# EAT0003.net
KiCad netlist of a schematic drawn in EAGLE
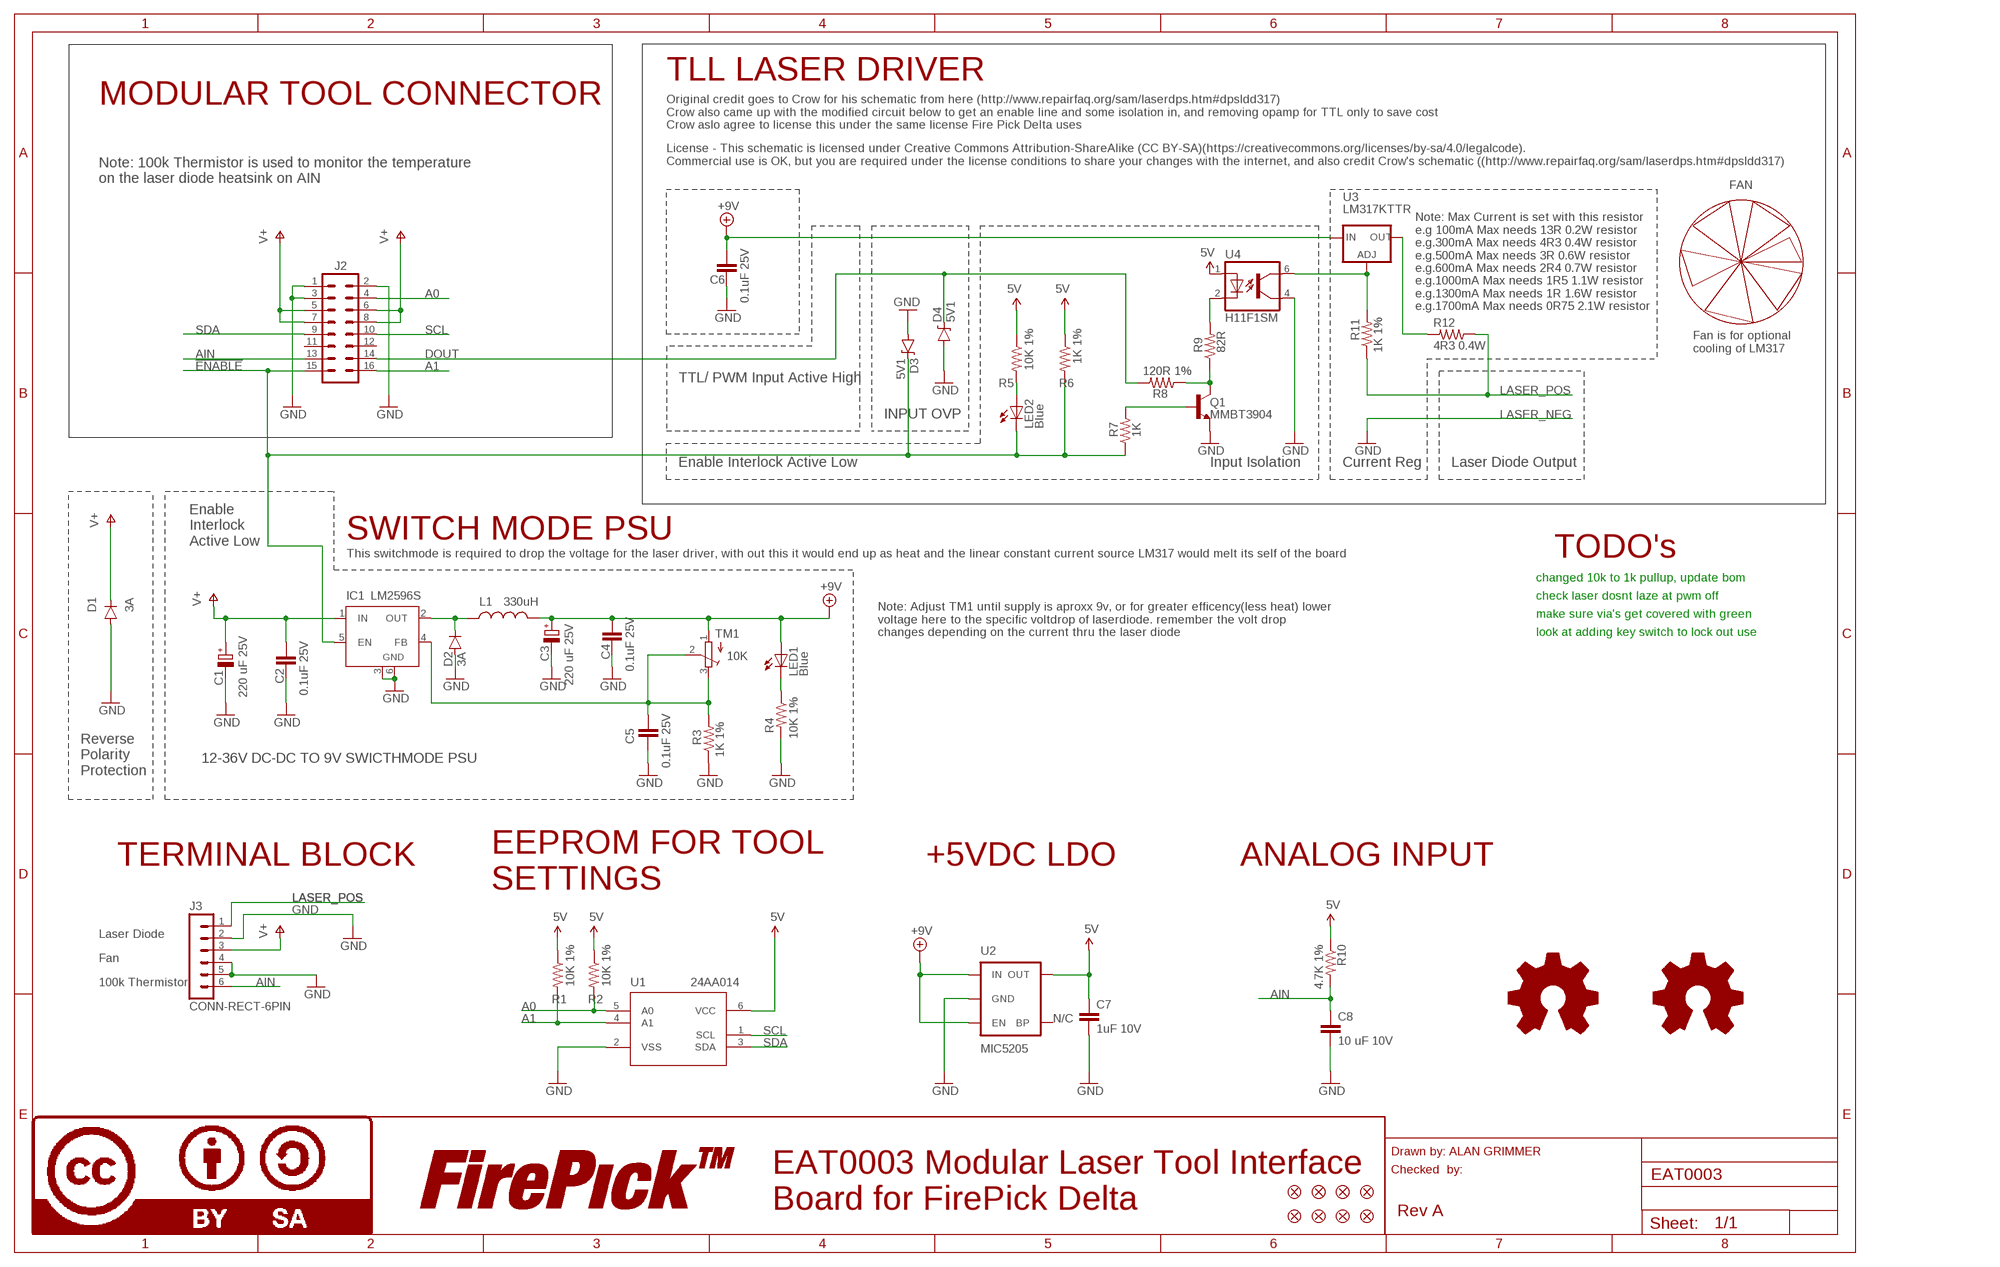
[diagram p0: schematic, sheet 1]

(export (version "E")
  (design (tool "Eeschema 10.0.6"))
  (components
    (comp (ref "C1")
      (value "220 uF 25V")
      (footprint "eagle-import:UD-8X10_NICHICON")
      (libsource (lib "eagle-import") (part "CPOL-EUUD-8X10"))
    )
    (comp (ref "C2")
      (value "0.1uF 25V")
      (footprint "eagle-import:0603-CAP")
      (libsource (lib "eagle-import") (part "CAP0603-CAP"))
    )
    (comp (ref "C3")
      (value "220 uF 25V")
      (footprint "eagle-import:UD-8X10_NICHICON")
      (libsource (lib "eagle-import") (part "CPOL-EUUD-8X10"))
    )
    (comp (ref "C4")
      (value "0.1uF 25V")
      (footprint "eagle-import:0603-CAP")
      (libsource (lib "eagle-import") (part "CAP0603-CAP"))
    )
    (comp (ref "C5")
      (value "0.1uF 25V")
      (footprint "eagle-import:0603-CAP")
      (libsource (lib "eagle-import") (part "CAP0603-CAP"))
    )
    (comp (ref "C6")
      (value "0.1uF 25V")
      (footprint "eagle-import:0603-CAP")
      (libsource (lib "eagle-import") (part "CAP0603-CAP"))
    )
    (comp (ref "C7")
      (value "1uF 10V")
      (footprint "eagle-import:0603-CAP")
      (libsource (lib "eagle-import") (part "CAP0603-CAP"))
    )
    (comp (ref "C8")
      (value "10 uF 10V")
      (footprint "eagle-import:0805")
      (libsource (lib "eagle-import") (part "CAP0805"))
    )
    (comp (ref "D1")
      (value "3A")
      (footprint "eagle-import:SMA-DIODE")
      (libsource (lib "eagle-import") (part "DIODESMA"))
    )
    (comp (ref "D2")
      (value "3A")
      (footprint "eagle-import:SMA-DIODE")
      (libsource (lib "eagle-import") (part "DIODESMA"))
    )
    (comp (ref "D3")
      (value "5V1")
      (footprint "eagle-import:SOD-323")
      (libsource (lib "eagle-import") (part "DIODE-ZENER5.6V"))
    )
    (comp (ref "D4")
      (value "5V1")
      (footprint "eagle-import:SOD-323")
      (libsource (lib "eagle-import") (part "DIODE-ZENER5.6V"))
    )
    (comp (ref "FAN1")
      (value "FAN_30MM")
      (footprint "eagle-import:FAN_30MM_X_30MM")
      (libsource (lib "eagle-import") (part "FAN_30MM"))
    )
    (comp (ref "FID1")
      (value "FIDUCIAL1X2")
      (footprint "eagle-import:FIDUCIAL-1X2")
      (libsource (lib "eagle-import") (part "FIDUCIAL1X2"))
    )
    (comp (ref "FID2")
      (value "FIDUCIAL1X2")
      (footprint "eagle-import:FIDUCIAL-1X2")
      (libsource (lib "eagle-import") (part "FIDUCIAL1X2"))
    )
    (comp (ref "FID3")
      (value "FIDUCIAL1X2")
      (footprint "eagle-import:FIDUCIAL-1X2")
      (libsource (lib "eagle-import") (part "FIDUCIAL1X2"))
    )
    (comp (ref "FID4")
      (value "FIDUCIAL1X2")
      (footprint "eagle-import:FIDUCIAL-1X2")
      (libsource (lib "eagle-import") (part "FIDUCIAL1X2"))
    )
    (comp (ref "FID5")
      (value "FIDUCIAL1X2")
      (footprint "eagle-import:FIDUCIAL-1X2")
      (libsource (lib "eagle-import") (part "FIDUCIAL1X2"))
    )
    (comp (ref "FID6")
      (value "FIDUCIAL1X2")
      (footprint "eagle-import:FIDUCIAL-1X2")
      (libsource (lib "eagle-import") (part "FIDUCIAL1X2"))
    )
    (comp (ref "FID7")
      (value "FIDUCIAL1X2")
      (footprint "eagle-import:FIDUCIAL-1X2")
      (libsource (lib "eagle-import") (part "FIDUCIAL1X2"))
    )
    (comp (ref "FID8")
      (value "FIDUCIAL1X2")
      (footprint "eagle-import:FIDUCIAL-1X2")
      (libsource (lib "eagle-import") (part "FIDUCIAL1X2"))
    )
    (comp (ref "IC1")
      (value "LM2596S")
      (footprint "eagle-import:TO263-5")
      (libsource (lib "eagle-import") (part "LM2596S"))
    )
    (comp (ref "J2")
      (value "CONN-RECT-16PIN-2ROWSIDE")
      (footprint "eagle-import:CONN-RECT-2.54MM-16PIN-2ROW-SIDE")
      (libsource (lib "eagle-import") (part "CONN-RECT-16PIN-2ROWSIDE"))
    )
    (comp (ref "J3")
      (value "CONN-RECT-6PIN")
      (footprint "eagle-import:CONN-OSTTE_6PIN")
      (libsource (lib "eagle-import") (part "CONN-RECT-6PIN"))
    )
    (comp (ref "L1")
      (value "330uH")
      (footprint "eagle-import:CDRH125")
      (libsource (lib "eagle-import") (part "INDUCTORPWR"))
    )
    (comp (ref "LED1")
      (value "Blue")
      (footprint "eagle-import:CHIPLED_0603")
      (libsource (lib "eagle-import") (part "LEDCHIPLED_0603"))
    )
    (comp (ref "LED2")
      (value "Blue")
      (footprint "eagle-import:CHIPLED_0603")
      (libsource (lib "eagle-import") (part "LEDCHIPLED_0603"))
    )
    (comp (ref "LOGO1")
      (value "LOGO-CC-BY-SASMALL")
      (footprint "eagle-import:LOGO-CC-BY-SA-SMALL")
      (libsource (lib "eagle-import") (part "LOGO-CC-BY-SASMALL"))
    )
    (comp (ref "LOGO2")
      (value "LOGO-FIREPICKSMALL")
      (footprint "eagle-import:LOGO-FIREPICK-SMALL")
      (libsource (lib "eagle-import") (part "LOGO-FIREPICKSMALL"))
    )
    (comp (ref "LOGO3")
      (value "LOGO-OSHWSMALL")
      (footprint "eagle-import:LOGO-OSHW-SMALL")
      (libsource (lib "eagle-import") (part "LOGO-OSHWSMALL"))
    )
    (comp (ref "LOGO4")
      (value "LOGO-OSHWSMALL")
      (footprint "eagle-import:LOGO-OSHW-SMALL")
      (libsource (lib "eagle-import") (part "LOGO-OSHWSMALL"))
    )
    (comp (ref "LOGO5")
      (value "LOGO-CC-BY-SASMALL")
      (footprint "eagle-import:LOGO-CC-BY-SA-SMALL")
      (libsource (lib "eagle-import") (part "LOGO-CC-BY-SASMALL"))
    )
    (comp (ref "LOGO6")
      (value "LOGO-FIREPICKSMALL")
      (footprint "eagle-import:LOGO-FIREPICK-SMALL")
      (libsource (lib "eagle-import") (part "LOGO-FIREPICKSMALL"))
    )
    (comp (ref "Q1")
      (value "MMBT3904")
      (footprint "eagle-import:SOT23-3")
      (libsource (lib "eagle-import") (part "TRANSISTOR_NPNMMBT2222A"))
    )
    (comp (ref "R1")
      (value "10K 1%")
      (footprint "eagle-import:0603-RES")
      (libsource (lib "eagle-import") (part "RESISTOR0603-RES"))
    )
    (comp (ref "R2")
      (value "10K 1%")
      (footprint "eagle-import:0603-RES")
      (libsource (lib "eagle-import") (part "RESISTOR0603-RES"))
    )
    (comp (ref "R3")
      (value "1K 1%")
      (footprint "eagle-import:0603-RES")
      (libsource (lib "eagle-import") (part "RESISTOR0603-RES"))
    )
    (comp (ref "R4")
      (value "10K 1%")
      (footprint "eagle-import:0603-RES")
      (libsource (lib "eagle-import") (part "RESISTOR0603-RES"))
    )
    (comp (ref "R5")
      (value "10K 1%")
      (footprint "eagle-import:0603-RES")
      (libsource (lib "eagle-import") (part "RESISTOR0603-RES"))
    )
    (comp (ref "R6")
      (value "1K 1%")
      (footprint "eagle-import:0603-RES")
      (libsource (lib "eagle-import") (part "RESISTOR0603-RES"))
    )
    (comp (ref "R7")
      (value "1K")
      (footprint "eagle-import:0603-RES")
      (libsource (lib "eagle-import") (part "RESISTOR0603-RES"))
    )
    (comp (ref "R8")
      (value "120R 1%")
      (footprint "eagle-import:0603-RES")
      (libsource (lib "eagle-import") (part "RESISTOR0603-RES"))
    )
    (comp (ref "R9")
      (value "82R")
      (footprint "eagle-import:0603-RES")
      (libsource (lib "eagle-import") (part "RESISTOR0603-RES"))
    )
    (comp (ref "R10")
      (value "4.7K 1%")
      (footprint "eagle-import:0603-RES")
      (libsource (lib "eagle-import") (part "RESISTOR0603-RES"))
    )
    (comp (ref "R11")
      (value "1K 1%")
      (footprint "eagle-import:0603-RES")
      (libsource (lib "eagle-import") (part "RESISTOR0603-RES"))
    )
    (comp (ref "R12")
      (value "4R3 0.4W")
      (footprint "eagle-import:R2512")
      (libsource (lib "eagle-import") (part "RESISTOR2512"))
    )
    (comp (ref "TM1")
      (value "10K")
      (footprint "eagle-import:TC33X")
      (libsource (lib "eagle-import") (part "TRIMPOTTC33X"))
    )
    (comp (ref "U1")
      (value "24AA014")
      (footprint "eagle-import:SOT23-6")
      (libsource (lib "eagle-import") (part "IC-24AA014"))
    )
    (comp (ref "U2")
      (value "MIC5205")
      (footprint "eagle-import:SOT23-5")
      (libsource (lib "eagle-import") (part "MIC52055V"))
    )
    (comp (ref "U3")
      (value "LM317KTTR")
      (footprint "eagle-import:D2PAK-3")
      (libsource (lib "eagle-import") (part "V_REG_317"))
    )
    (comp (ref "U4")
      (value "H11F1SM")
      (footprint "eagle-import:DIL6-SMD")
      (libsource (lib "eagle-import") (part "H11F1DIL6SMD"))
    )
  )
  (nets
    (net (code "1") (name "+9V") (class "Default")
      (node (ref "C3") (pin "+") (pinfunction "+_+") (pintype "passive"))
      (node (ref "C4") (pin "1") (pinfunction "1_1") (pintype "passive"))
      (node (ref "C6") (pin "1") (pinfunction "1_1") (pintype "passive"))
      (node (ref "L1") (pin "2") (pinfunction "2_2") (pintype "passive"))
      (node (ref "LED1") (pin "A") (pinfunction "A_A") (pintype "passive"))
      (node (ref "TM1") (pin "1") (pinfunction "A_1") (pintype "passive"))
      (node (ref "U2") (pin "1") (pinfunction "IN_1") (pintype "input"))
      (node (ref "U2") (pin "3") (pinfunction "EN_3") (pintype "input"))
      (node (ref "U3") (pin "3") (pinfunction "IN_3") (pintype "input"))
    )
    (net (code "2") (name "/A0") (class "Default")
      (node (ref "J2") (pin "4") (pinfunction "4_4") (pintype "passive"))
      (node (ref "R2") (pin "2") (pinfunction "2_2") (pintype "passive"))
      (node (ref "U1") (pin "5") (pinfunction "A0_5") (pintype "bidirectional"))
    )
    (net (code "3") (name "/A1") (class "Default")
      (node (ref "J2") (pin "16") (pinfunction "16_16") (pintype "passive"))
      (node (ref "R1") (pin "2") (pinfunction "2_2") (pintype "passive"))
      (node (ref "U1") (pin "4") (pinfunction "A1_4") (pintype "bidirectional"))
    )
    (net (code "4") (name "/AIN") (class "Default")
      (node (ref "C8") (pin "1") (pinfunction "1_1") (pintype "passive"))
      (node (ref "J2") (pin "13") (pinfunction "13_13") (pintype "passive"))
      (node (ref "J3") (pin "6") (pinfunction "6_6") (pintype "passive"))
      (node (ref "R10") (pin "2") (pinfunction "2_2") (pintype "passive"))
    )
    (net (code "5") (name "/DOUT") (class "Default")
      (node (ref "D4") (pin "C") (pinfunction "C_C") (pintype "passive"))
      (node (ref "J2") (pin "14") (pinfunction "14_14") (pintype "passive"))
      (node (ref "R8") (pin "2") (pinfunction "2_2") (pintype "passive"))
    )
    (net (code "6") (name "/LASER_POS") (class "Default")
      (node (ref "J3") (pin "1") (pinfunction "1_1") (pintype "passive"))
      (node (ref "R11") (pin "1") (pinfunction "1_1") (pintype "passive"))
      (node (ref "R12") (pin "1") (pinfunction "1_1") (pintype "passive"))
    )
    (net (code "7") (name "/SCL") (class "Default")
      (node (ref "J2") (pin "10") (pinfunction "10_10") (pintype "passive"))
      (node (ref "U1") (pin "1") (pinfunction "SCL_1") (pintype "bidirectional"))
    )
    (net (code "8") (name "/SDA") (class "Default")
      (node (ref "J2") (pin "9") (pinfunction "9_9") (pintype "passive"))
      (node (ref "U1") (pin "3") (pinfunction "SDA_3") (pintype "bidirectional"))
    )
    (net (code "9") (name "/~{ENABLE}") (class "Default")
      (node (ref "D3") (pin "C") (pinfunction "C_C") (pintype "passive"))
      (node (ref "IC1") (pin "5") (pinfunction "EN_5") (pintype "input"))
      (node (ref "J2") (pin "15") (pinfunction "15_15") (pintype "passive"))
      (node (ref "LED2") (pin "C") (pinfunction "C_C") (pintype "passive"))
      (node (ref "R6") (pin "2") (pinfunction "2_2") (pintype "passive"))
      (node (ref "R7") (pin "1") (pinfunction "1_1") (pintype "passive"))
    )
    (net (code "10") (name "5V") (class "Default")
      (node (ref "C7") (pin "1") (pinfunction "1_1") (pintype "passive"))
      (node (ref "R1") (pin "1") (pinfunction "1_1") (pintype "passive"))
      (node (ref "R10") (pin "1") (pinfunction "1_1") (pintype "passive"))
      (node (ref "R2") (pin "1") (pinfunction "1_1") (pintype "passive"))
      (node (ref "R5") (pin "1") (pinfunction "1_1") (pintype "passive"))
      (node (ref "R6") (pin "1") (pinfunction "1_1") (pintype "passive"))
      (node (ref "U1") (pin "6") (pinfunction "VCC_6") (pintype "bidirectional"))
      (node (ref "U2") (pin "5") (pinfunction "OUT_5") (pintype "passive"))
      (node (ref "U4") (pin "1") (pinfunction "A_1") (pintype "passive"))
    )
    (net (code "11") (name "GND") (class "Default")
      (node (ref "C1") (pin "-") (pinfunction "-_-") (pintype "passive"))
      (node (ref "C2") (pin "2") (pinfunction "2_2") (pintype "passive"))
      (node (ref "C3") (pin "-") (pinfunction "-_-") (pintype "passive"))
      (node (ref "C4") (pin "2") (pinfunction "2_2") (pintype "passive"))
      (node (ref "C5") (pin "2") (pinfunction "2_2") (pintype "passive"))
      (node (ref "C6") (pin "2") (pinfunction "2_2") (pintype "passive"))
      (node (ref "C7") (pin "2") (pinfunction "2_2") (pintype "passive"))
      (node (ref "C8") (pin "2") (pinfunction "2_2") (pintype "passive"))
      (node (ref "D1") (pin "A") (pinfunction "A_A") (pintype "passive"))
      (node (ref "D2") (pin "A") (pinfunction "A_A") (pintype "passive"))
      (node (ref "D3") (pin "A") (pinfunction "A_A") (pintype "passive"))
      (node (ref "D4") (pin "A") (pinfunction "A_A") (pintype "passive"))
      (node (ref "IC1") (pin "3") (pinfunction "GND_3") (pintype "power_in"))
      (node (ref "IC1") (pin "6") (pinfunction "GND_6") (pintype "power_in"))
      (node (ref "J2") (pin "1") (pinfunction "1_1") (pintype "passive"))
      (node (ref "J2") (pin "2") (pinfunction "2_2") (pintype "passive"))
      (node (ref "J2") (pin "3") (pinfunction "3_3") (pintype "passive"))
      (node (ref "J3") (pin "2") (pinfunction "2_2") (pintype "passive"))
      (node (ref "J3") (pin "4") (pinfunction "4_4") (pintype "passive"))
      (node (ref "J3") (pin "5") (pinfunction "5_5") (pintype "passive"))
      (node (ref "Q1") (pin "2") (pinfunction "E_2") (pintype "passive"))
      (node (ref "R3") (pin "1") (pinfunction "1_1") (pintype "passive"))
      (node (ref "R4") (pin "2") (pinfunction "2_2") (pintype "passive"))
      (node (ref "U1") (pin "2") (pinfunction "VSS_2") (pintype "bidirectional"))
      (node (ref "U2") (pin "2") (pinfunction "GND_2") (pintype "input"))
      (node (ref "U4") (pin "4") (pinfunction "EMIT_4") (pintype "passive"))
    )
    (net (code "12") (name "Net-(IC1-FB)") (class "Default")
      (node (ref "C5") (pin "1") (pinfunction "1_1") (pintype "passive"))
      (node (ref "IC1") (pin "4") (pinfunction "FB_4") (pintype "input"))
      (node (ref "R3") (pin "2") (pinfunction "2_2") (pintype "passive"))
      (node (ref "TM1") (pin "2") (pinfunction "S_2") (pintype "passive"))
      (node (ref "TM1") (pin "3") (pinfunction "E_3") (pintype "passive"))
    )
    (net (code "13") (name "Net-(IC1-OUT)") (class "Default")
      (node (ref "D2") (pin "C") (pinfunction "C_C") (pintype "passive"))
      (node (ref "IC1") (pin "2") (pinfunction "OUT_2") (pintype "output"))
      (node (ref "L1") (pin "1") (pinfunction "1_1") (pintype "passive"))
    )
    (net (code "14") (name "Net-(LED1-PadC)") (class "Default")
      (node (ref "LED1") (pin "C") (pinfunction "C_C") (pintype "passive"))
      (node (ref "R4") (pin "1") (pinfunction "1_1") (pintype "passive"))
    )
    (net (code "15") (name "Net-(LED2-PadA)") (class "Default")
      (node (ref "LED2") (pin "A") (pinfunction "A_A") (pintype "passive"))
      (node (ref "R5") (pin "2") (pinfunction "2_2") (pintype "passive"))
    )
    (net (code "16") (name "Net-(Q1-B)") (class "Default")
      (node (ref "Q1") (pin "1") (pinfunction "B_1") (pintype "passive"))
      (node (ref "R7") (pin "2") (pinfunction "2_2") (pintype "passive"))
    )
    (net (code "17") (name "Net-(Q1-C)") (class "Default")
      (node (ref "Q1") (pin "3") (pinfunction "C_3") (pintype "passive"))
      (node (ref "R8") (pin "1") (pinfunction "1_1") (pintype "passive"))
      (node (ref "R9") (pin "1") (pinfunction "1_1") (pintype "passive"))
    )
    (net (code "18") (name "Net-(R12-Pad2)") (class "Default")
      (node (ref "R12") (pin "2") (pinfunction "2_2") (pintype "passive"))
      (node (ref "U3") (pin "2") (pinfunction "OUT_2") (pintype "output"))
      (node (ref "U3") (pin "PAD") (pinfunction "OUT_PAD") (pintype "output"))
    )
    (net (code "19") (name "Net-(U3-ADJ)") (class "Default")
      (node (ref "R11") (pin "2") (pinfunction "2_2") (pintype "passive"))
      (node (ref "U3") (pin "1") (pinfunction "ADJ_1") (pintype "input"))
      (node (ref "U4") (pin "6") (pinfunction "COL_6") (pintype "passive"))
    )
    (net (code "20") (name "Net-(U4-C)") (class "Default")
      (node (ref "R9") (pin "2") (pinfunction "2_2") (pintype "passive"))
      (node (ref "U4") (pin "2") (pinfunction "C_2") (pintype "passive"))
    )
    (net (code "21") (name "V+") (class "Default")
      (node (ref "C1") (pin "+") (pinfunction "+_+") (pintype "passive"))
      (node (ref "C2") (pin "1") (pinfunction "1_1") (pintype "passive"))
      (node (ref "D1") (pin "C") (pinfunction "C_C") (pintype "passive"))
      (node (ref "IC1") (pin "1") (pinfunction "IN_1") (pintype "input"))
      (node (ref "J2") (pin "5") (pinfunction "5_5") (pintype "passive"))
      (node (ref "J2") (pin "6") (pinfunction "6_6") (pintype "passive"))
      (node (ref "J2") (pin "7") (pinfunction "7_7") (pintype "passive"))
      (node (ref "J2") (pin "8") (pinfunction "8_8") (pintype "passive"))
      (node (ref "J3") (pin "3") (pinfunction "3_3") (pintype "passive"))
    )
    (net (code "22") (name "unconnected-(J2-Pad11)") (class "Default")
      (node (ref "J2") (pin "11") (pinfunction "11_11") (pintype "passive"))
    )
    (net (code "23") (name "unconnected-(J2-Pad12)") (class "Default")
      (node (ref "J2") (pin "12") (pinfunction "12_12") (pintype "passive"))
    )
    (net (code "24") (name "unconnected-(U2-BP-Pad4)") (class "Default")
      (node (ref "U2") (pin "4") (pinfunction "BP_4") (pintype "input"))
    )
  )
)
